# M32W_v1_0.net
KiCad netlist of a schematic drawn in EAGLE
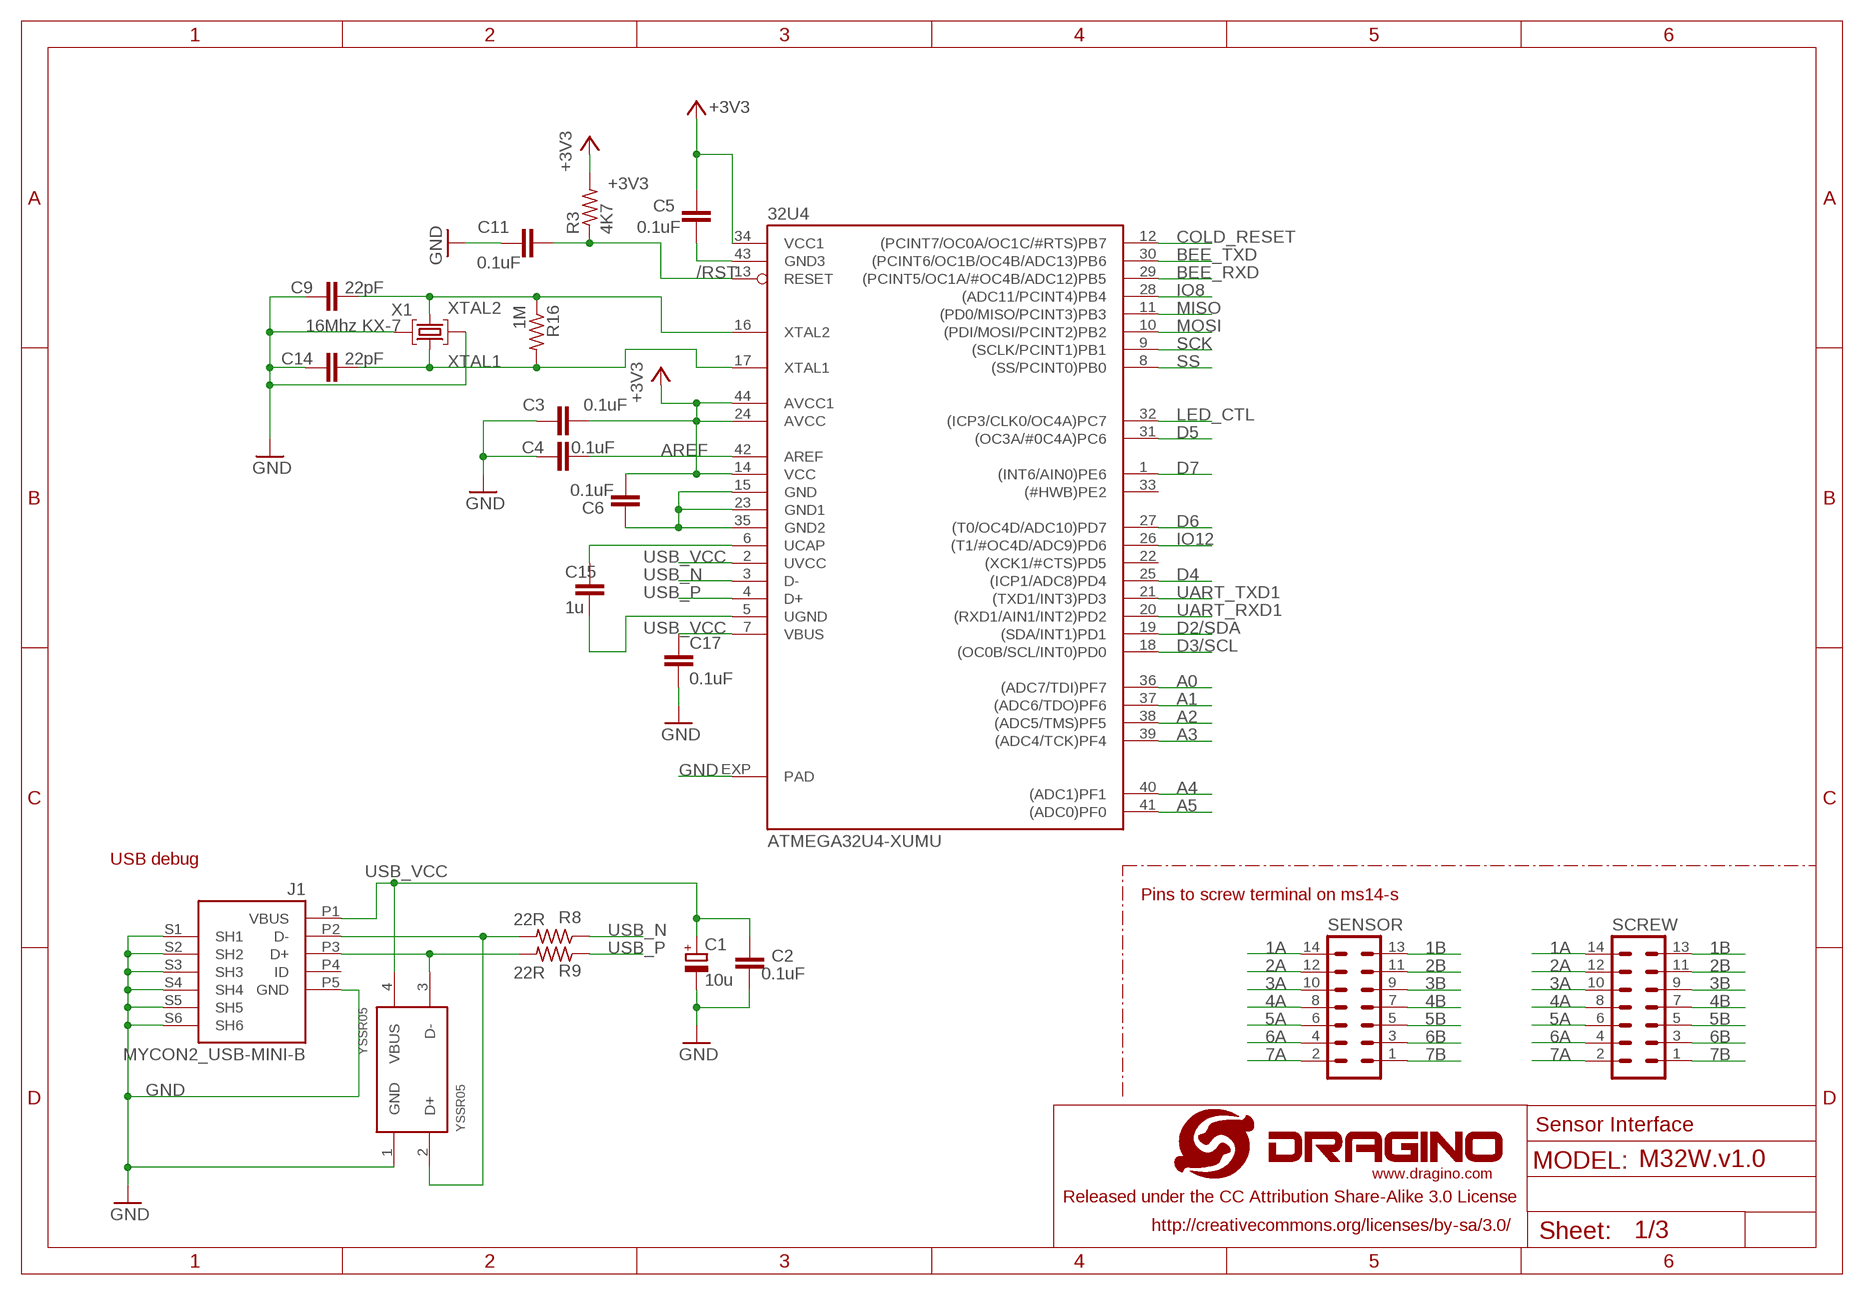
[diagram p0: schematic, sheet 1]
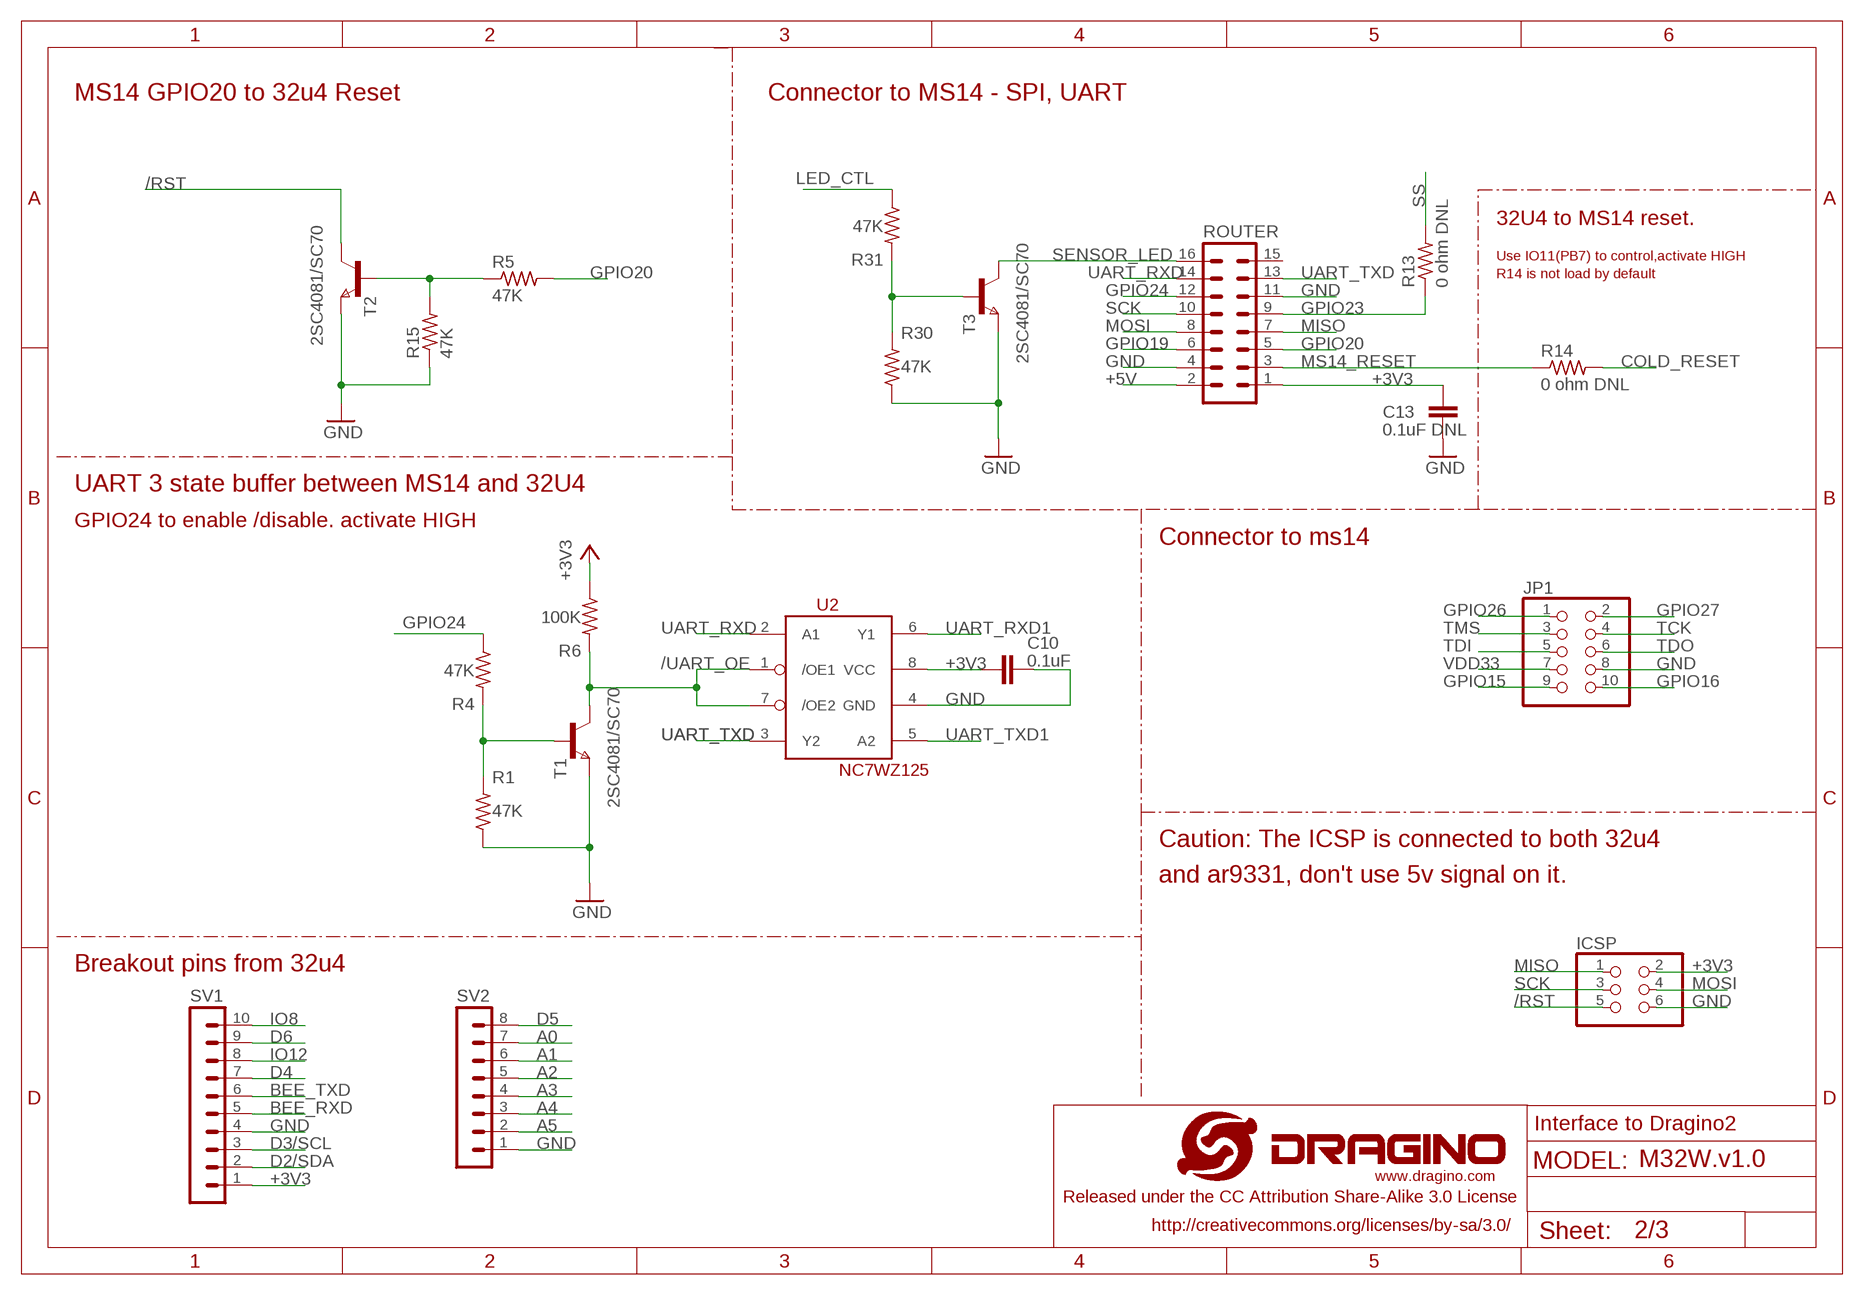
[diagram p1: schematic, sheet 2]
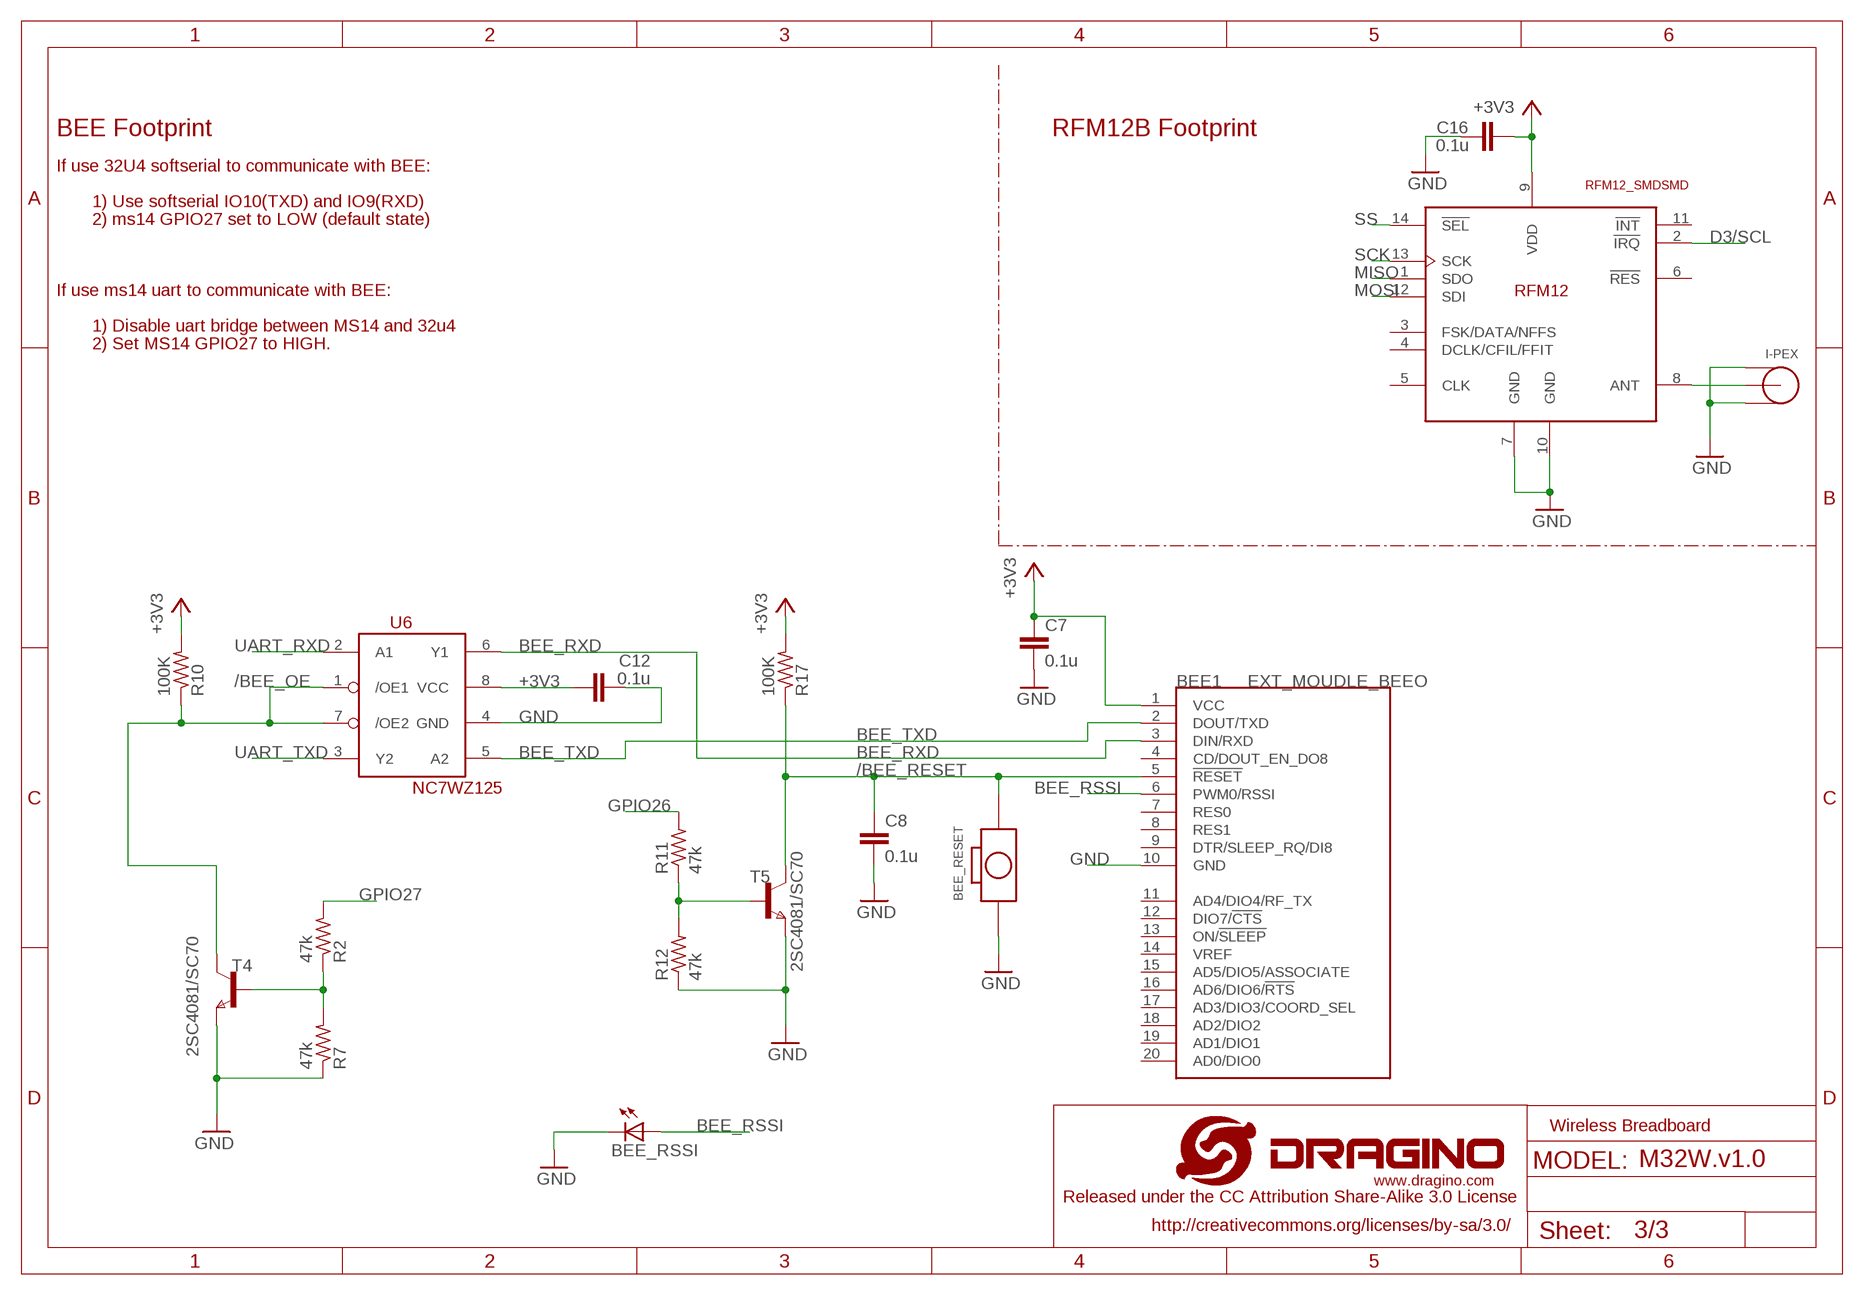
[diagram p2: schematic, sheet 3]

(export (version "E")
  (design (tool "Eeschema 10.0.6"))
  (components
    (comp (ref "32U4")
      (value "ATMEGA32U4-XUMU")
      (footprint "eagle-import:QFN44ML7X7")
      (libsource (lib "eagle-import") (part "ATMEGA32U4-XUMU"))
    )
    (comp (ref "C1")
      (value "10u")
      (footprint "eagle-import:SMC_B")
      (libsource (lib "eagle-import") (part "CPOL-EUSMCB"))
    )
    (comp (ref "C2")
      (value "0.1uF")
      (footprint "eagle-import:C0402")
      (libsource (lib "eagle-import") (part "C-EUC0402"))
    )
    (comp (ref "C3")
      (value "0.1uF")
      (footprint "eagle-import:C0402")
      (libsource (lib "eagle-import") (part "C-EUC0402"))
    )
    (comp (ref "C4")
      (value "0.1uF")
      (footprint "eagle-import:C0402")
      (libsource (lib "eagle-import") (part "C-EUC0402"))
    )
    (comp (ref "C5")
      (value "0.1uF")
      (footprint "eagle-import:C0402")
      (libsource (lib "eagle-import") (part "C-EUC0402"))
    )
    (comp (ref "C6")
      (value "0.1uF")
      (footprint "eagle-import:C0402")
      (libsource (lib "eagle-import") (part "C-EUC0402"))
    )
    (comp (ref "C9")
      (value "22pF")
      (footprint "eagle-import:C0402")
      (libsource (lib "eagle-import") (part "C-EUC0402"))
    )
    (comp (ref "C11")
      (value "0.1uF")
      (footprint "eagle-import:C0402")
      (libsource (lib "eagle-import") (part "C-EUC0402"))
    )
    (comp (ref "C14")
      (value "22pF")
      (footprint "eagle-import:C0402")
      (libsource (lib "eagle-import") (part "C-EUC0402"))
    )
    (comp (ref "C15")
      (value "1u")
      (footprint "eagle-import:C0402")
      (libsource (lib "eagle-import") (part "C-EUC0402"))
    )
    (comp (ref "C17")
      (value "0.1uF")
      (footprint "eagle-import:C0402")
      (libsource (lib "eagle-import") (part "C-EUC0402"))
    )
    (comp (ref "J1")
      (value "MYCON2_USB-MINI-B")
      (footprint "eagle-import:CON2_USB_MICRO_B_AT")
      (libsource (lib "eagle-import") (part "MYCON2_USB-MINI-B"))
    )
    (comp (ref "R3")
      (value "4K7")
      (footprint "eagle-import:R0402")
      (libsource (lib "eagle-import") (part "R-US_R0402"))
    )
    (comp (ref "R8")
      (value "22R")
      (footprint "eagle-import:R0402")
      (libsource (lib "eagle-import") (part "R-US_R0402"))
    )
    (comp (ref "R9")
      (value "22R")
      (footprint "eagle-import:R0402")
      (libsource (lib "eagle-import") (part "R-US_R0402"))
    )
    (comp (ref "R16")
      (value "1M")
      (footprint "eagle-import:R0402")
      (libsource (lib "eagle-import") (part "R-US_R0402"))
    )
    (comp (ref "SCREW")
      (value "MA07-2")
      (footprint "eagle-import:MA07-2")
      (fields (field (name "OC_FARNELL") "unknown") (field (name "OC_NEWARK") "unknown"))
      (libsource (lib "eagle-import") (part "MA07-2"))
    )
    (comp (ref "SENSOR")
      (value "MA07-2")
      (footprint "eagle-import:MA07-2")
      (libsource (lib "eagle-import") (part "MA07-2"))
    )
    (comp (ref "X1")
      (value "16Mhz KX-7")
      (footprint "eagle-import:CRYSTAL-3.2-2.5")
      (libsource (lib "eagle-import") (part "CRYSTAL-3.2-2.5"))
    )
    (comp (ref "YSSR05")
      (value "YSSR05")
      (footprint "eagle-import:SOT143")
      (libsource (lib "eagle-import") (part "YSSR05"))
    )
    (comp (ref "C10")
      (value "0.1uF")
      (footprint "eagle-import:C0402")
      (libsource (lib "eagle-import") (part "C-EUC0402"))
    )
    (comp (ref "C13")
      (value "0.1uF DNL")
      (footprint "eagle-import:C0402")
      (libsource (lib "eagle-import") (part "C-EUC0402"))
    )
    (comp (ref "ICSP")
      (value "PINHD-2X3")
      (footprint "eagle-import:2X03")
      (libsource (lib "eagle-import") (part "PINHD-2X3"))
    )
    (comp (ref "JP1")
      (value "PINHD-2X5_2.00")
      (footprint "eagle-import:2X05M")
      (libsource (lib "eagle-import") (part "PINHD-2X5_2.00"))
    )
    (comp (ref "R1")
      (value "47K")
      (footprint "eagle-import:R0402")
      (libsource (lib "eagle-import") (part "R-US_R0402"))
    )
    (comp (ref "R4")
      (value "47K")
      (footprint "eagle-import:R0402")
      (libsource (lib "eagle-import") (part "R-US_R0402"))
    )
    (comp (ref "R5")
      (value "47K")
      (footprint "eagle-import:R0402")
      (libsource (lib "eagle-import") (part "R-US_R0402"))
    )
    (comp (ref "R6")
      (value "100K")
      (footprint "eagle-import:R0402")
      (libsource (lib "eagle-import") (part "R-US_R0402"))
    )
    (comp (ref "R13")
      (value "0 ohm DNL")
      (footprint "eagle-import:R0402")
      (libsource (lib "eagle-import") (part "R-US_R0402"))
    )
    (comp (ref "R14")
      (value "0 ohm DNL")
      (footprint "eagle-import:R0402")
      (libsource (lib "eagle-import") (part "R-US_R0402"))
    )
    (comp (ref "R15")
      (value "47K")
      (footprint "eagle-import:R0402")
      (libsource (lib "eagle-import") (part "R-US_R0402"))
    )
    (comp (ref "R30")
      (value "47K")
      (footprint "eagle-import:R0402")
      (libsource (lib "eagle-import") (part "R-US_R0402"))
    )
    (comp (ref "R31")
      (value "47K")
      (footprint "eagle-import:R0402")
      (libsource (lib "eagle-import") (part "R-US_R0402"))
    )
    (comp (ref "ROUTER")
      (value "MA08-2")
      (footprint "eagle-import:MA08-2")
      (libsource (lib "eagle-import") (part "MA08-2"))
    )
    (comp (ref "SV1")
      (value "MA10-1")
      (footprint "eagle-import:MA10-1")
      (libsource (lib "eagle-import") (part "MA10-1"))
    )
    (comp (ref "SV2")
      (value "MA08-1")
      (footprint "eagle-import:MA08-1")
      (libsource (lib "eagle-import") (part "MA08-1"))
    )
    (comp (ref "T1")
      (value "2SC4081/SC70")
      (footprint "eagle-import:SOT323")
      (fields (field (name "MPN") "DSS4160U-7"))
      (libsource (lib "eagle-import") (part "NPNSOT323"))
    )
    (comp (ref "T2")
      (value "2SC4081/SC70")
      (footprint "eagle-import:SOT323")
      (fields
        (field (name "MPN") "DSS4160U-7")
        (field (name "MPN_1") "DSS4160U-7")
        (field (name "OC_FARNELL") "1710696")
        (field (name "OC_NEWARK") "25R4558")
      )
      (libsource (lib "eagle-import") (part "NPNSOT323"))
    )
    (comp (ref "T3")
      (value "2SC4081/SC70")
      (footprint "eagle-import:SOT323")
      (fields (field (name "MPN") "DSS4160U-7"))
      (libsource (lib "eagle-import") (part "NPNSOT323"))
    )
    (comp (ref "U$5")
      (value "LOGO-NEW")
      (footprint "eagle-import:LOGO-SILK-NEW")
      (libsource (lib "eagle-import") (part "LOGO-NEW"))
    )
    (comp (ref "U2")
      (value "NC7WZ125")
      (footprint "eagle-import:US8")
      (libsource (lib "eagle-import") (part "NC7WZ125"))
    )
    (comp (ref "BEE1")
      (value "EXT_MOUDLE_BEEO")
      (footprint "eagle-import:EXT_MOUDLE_BEE")
      (libsource (lib "eagle-import") (part "EXT_MOUDLE_BEEO"))
    )
    (comp (ref "BEE_RESET")
      (value "CPT_SMD_BOTTON_1_SMD")
      (footprint "eagle-import:CPT_SMD_BOTTON_1")
      (libsource (lib "eagle-import") (part "CPT_SMD_BOTTON_1_SMD"))
    )
    (comp (ref "BEE_RSSI")
      (value "LEDCHIP-LED0805")
      (footprint "eagle-import:CHIP-LED0805")
      (libsource (lib "eagle-import") (part "LEDCHIP-LED0805"))
    )
    (comp (ref "C7")
      (value "0.1u")
      (footprint "eagle-import:C0402")
      (libsource (lib "eagle-import") (part "C-EUC0402"))
    )
    (comp (ref "C8")
      (value "0.1u")
      (footprint "eagle-import:C0402")
      (libsource (lib "eagle-import") (part "C-EUC0402"))
    )
    (comp (ref "C12")
      (value "0.1u")
      (footprint "eagle-import:C0402")
      (libsource (lib "eagle-import") (part "C-EUC0402"))
    )
    (comp (ref "C16")
      (value "0.1u")
      (footprint "eagle-import:C0402")
      (libsource (lib "eagle-import") (part "C-EUC0402"))
    )
    (comp (ref "I-PEX")
      (value "I-PEX")
      (footprint "eagle-import:I-PEX")
      (libsource (lib "eagle-import") (part "I-PEX"))
    )
    (comp (ref "R2")
      (value "47k")
      (footprint "eagle-import:R0402")
      (libsource (lib "eagle-import") (part "R-US_R0402"))
    )
    (comp (ref "R7")
      (value "47k")
      (footprint "eagle-import:R0402")
      (libsource (lib "eagle-import") (part "R-US_R0402"))
    )
    (comp (ref "R10")
      (value "100K")
      (footprint "eagle-import:R0402")
      (libsource (lib "eagle-import") (part "R-US_R0402"))
    )
    (comp (ref "R11")
      (value "47k")
      (footprint "eagle-import:R0402")
      (libsource (lib "eagle-import") (part "R-US_R0402"))
    )
    (comp (ref "R12")
      (value "47k")
      (footprint "eagle-import:R0402")
      (libsource (lib "eagle-import") (part "R-US_R0402"))
    )
    (comp (ref "R17")
      (value "100K")
      (footprint "eagle-import:R0402")
      (libsource (lib "eagle-import") (part "R-US_R0402"))
    )
    (comp (ref "T4")
      (value "2SC4081/SC70")
      (footprint "eagle-import:SOT323")
      (fields (field (name "MPN") "DSS4160U-7"))
      (libsource (lib "eagle-import") (part "NPNSOT323"))
    )
    (comp (ref "T5")
      (value "2SC4081/SC70")
      (footprint "eagle-import:SOT323")
      (fields (field (name "MPN") "DSS4160U-7"))
      (libsource (lib "eagle-import") (part "NPNSOT323"))
    )
    (comp (ref "U$3")
      (value "RFM12_SMDSMD")
      (footprint "eagle-import:RFM12")
      (libsource (lib "eagle-import") (part "RFM12_SMDSMD"))
    )
    (comp (ref "U6")
      (value "NC7WZ125")
      (footprint "eagle-import:US8")
      (libsource (lib "eagle-import") (part "NC7WZ125"))
    )
  )
  (nets
    (net (code "1") (name "+3V3") (class "Default")
      (node (ref "32U4") (pin "14") (pinfunction "VCC_14") (pintype "power_in"))
      (node (ref "32U4") (pin "24") (pinfunction "AVCC_24") (pintype "power_in"))
      (node (ref "32U4") (pin "34") (pinfunction "VCC1_34") (pintype "power_in"))
      (node (ref "32U4") (pin "44") (pinfunction "AVCC1_44") (pintype "power_in"))
      (node (ref "BEE1") (pin "1") (pinfunction "VCC_1") (pintype "bidirectional"))
      (node (ref "C10") (pin "2") (pinfunction "2_2") (pintype "passive"))
      (node (ref "C12") (pin "1") (pinfunction "1_1") (pintype "passive"))
      (node (ref "C13") (pin "1") (pinfunction "1_1") (pintype "passive"))
      (node (ref "C16") (pin "2") (pinfunction "2_2") (pintype "passive"))
      (node (ref "C3") (pin "2") (pinfunction "2_2") (pintype "passive"))
      (node (ref "C5") (pin "1") (pinfunction "1_1") (pintype "passive"))
      (node (ref "C6") (pin "2") (pinfunction "2_2") (pintype "passive"))
      (node (ref "C7") (pin "1") (pinfunction "1_1") (pintype "passive"))
      (node (ref "ICSP") (pin "2") (pinfunction "2_2") (pintype "passive"))
      (node (ref "R10") (pin "2") (pinfunction "2_2") (pintype "passive"))
      (node (ref "R17") (pin "2") (pinfunction "2_2") (pintype "passive"))
      (node (ref "R3") (pin "2") (pinfunction "2_2") (pintype "passive"))
      (node (ref "R6") (pin "1") (pinfunction "1_1") (pintype "passive"))
      (node (ref "ROUTER") (pin "1") (pinfunction "1_1") (pintype "passive"))
      (node (ref "SV1") (pin "1") (pinfunction "1_1") (pintype "passive"))
      (node (ref "U$3") (pin "9") (pinfunction "VDD_9") (pintype "power_in"))
      (node (ref "U2") (pin "8") (pinfunction "VCC_8") (pintype "power_in"))
      (node (ref "U6") (pin "8") (pinfunction "VCC_8") (pintype "power_in"))
    )
    (net (code "2") (name "+5V") (class "Default")
      (node (ref "ROUTER") (pin "2") (pinfunction "2_2") (pintype "passive"))
    )
    (net (code "3") (name "1A") (class "Default")
      (node (ref "SCREW") (pin "14") (pinfunction "14_14") (pintype "passive"))
      (node (ref "SENSOR") (pin "14") (pinfunction "14_14") (pintype "passive"))
    )
    (net (code "4") (name "1B") (class "Default")
      (node (ref "SCREW") (pin "13") (pinfunction "13_13") (pintype "passive"))
      (node (ref "SENSOR") (pin "13") (pinfunction "13_13") (pintype "passive"))
    )
    (net (code "5") (name "2A") (class "Default")
      (node (ref "SCREW") (pin "12") (pinfunction "12_12") (pintype "passive"))
      (node (ref "SENSOR") (pin "12") (pinfunction "12_12") (pintype "passive"))
    )
    (net (code "6") (name "2B") (class "Default")
      (node (ref "SCREW") (pin "11") (pinfunction "11_11") (pintype "passive"))
      (node (ref "SENSOR") (pin "11") (pinfunction "11_11") (pintype "passive"))
    )
    (net (code "7") (name "3A") (class "Default")
      (node (ref "SCREW") (pin "10") (pinfunction "10_10") (pintype "passive"))
      (node (ref "SENSOR") (pin "10") (pinfunction "10_10") (pintype "passive"))
    )
    (net (code "8") (name "3B") (class "Default")
      (node (ref "SCREW") (pin "9") (pinfunction "9_9") (pintype "passive"))
      (node (ref "SENSOR") (pin "9") (pinfunction "9_9") (pintype "passive"))
    )
    (net (code "9") (name "4A") (class "Default")
      (node (ref "SCREW") (pin "8") (pinfunction "8_8") (pintype "passive"))
      (node (ref "SENSOR") (pin "8") (pinfunction "8_8") (pintype "passive"))
    )
    (net (code "10") (name "4B") (class "Default")
      (node (ref "SCREW") (pin "7") (pinfunction "7_7") (pintype "passive"))
      (node (ref "SENSOR") (pin "7") (pinfunction "7_7") (pintype "passive"))
    )
    (net (code "11") (name "5A") (class "Default")
      (node (ref "SCREW") (pin "6") (pinfunction "6_6") (pintype "passive"))
      (node (ref "SENSOR") (pin "6") (pinfunction "6_6") (pintype "passive"))
    )
    (net (code "12") (name "5B") (class "Default")
      (node (ref "SCREW") (pin "5") (pinfunction "5_5") (pintype "passive"))
      (node (ref "SENSOR") (pin "5") (pinfunction "5_5") (pintype "passive"))
    )
    (net (code "13") (name "6A") (class "Default")
      (node (ref "SCREW") (pin "4") (pinfunction "4_4") (pintype "passive"))
      (node (ref "SENSOR") (pin "4") (pinfunction "4_4") (pintype "passive"))
    )
    (net (code "14") (name "6B") (class "Default")
      (node (ref "SCREW") (pin "3") (pinfunction "3_3") (pintype "passive"))
      (node (ref "SENSOR") (pin "3") (pinfunction "3_3") (pintype "passive"))
    )
    (net (code "15") (name "7A") (class "Default")
      (node (ref "SCREW") (pin "2") (pinfunction "2_2") (pintype "passive"))
      (node (ref "SENSOR") (pin "2") (pinfunction "2_2") (pintype "passive"))
    )
    (net (code "16") (name "7B") (class "Default")
      (node (ref "SCREW") (pin "1") (pinfunction "1_1") (pintype "passive"))
      (node (ref "SENSOR") (pin "1") (pinfunction "1_1") (pintype "passive"))
    )
    (net (code "17") (name "A0") (class "Default")
      (node (ref "32U4") (pin "36") (pinfunction "(ADC7/TDI)PF7_36") (pintype "bidirectional"))
      (node (ref "SV2") (pin "7") (pinfunction "7_7") (pintype "passive"))
    )
    (net (code "18") (name "A1") (class "Default")
      (node (ref "32U4") (pin "37") (pinfunction "(ADC6/TDO)PF6_37") (pintype "bidirectional"))
      (node (ref "SV2") (pin "6") (pinfunction "6_6") (pintype "passive"))
    )
    (net (code "19") (name "A2") (class "Default")
      (node (ref "32U4") (pin "38") (pinfunction "(ADC5/TMS)PF5_38") (pintype "bidirectional"))
      (node (ref "SV2") (pin "5") (pinfunction "5_5") (pintype "passive"))
    )
    (net (code "20") (name "A3") (class "Default")
      (node (ref "32U4") (pin "39") (pinfunction "(ADC4/TCK)PF4_39") (pintype "bidirectional"))
      (node (ref "SV2") (pin "4") (pinfunction "4_4") (pintype "passive"))
    )
    (net (code "21") (name "A4") (class "Default")
      (node (ref "32U4") (pin "40") (pinfunction "(ADC1)PF1_40") (pintype "bidirectional"))
      (node (ref "SV2") (pin "3") (pinfunction "3_3") (pintype "passive"))
    )
    (net (code "22") (name "A5") (class "Default")
      (node (ref "32U4") (pin "41") (pinfunction "(ADC0)PF0_41") (pintype "bidirectional"))
      (node (ref "SV2") (pin "2") (pinfunction "2_2") (pintype "passive"))
    )
    (net (code "23") (name "AREF") (class "Default")
      (node (ref "32U4") (pin "42") (pinfunction "AREF_42") (pintype "power_in"))
      (node (ref "C4") (pin "2") (pinfunction "2_2") (pintype "passive"))
    )
    (net (code "24") (name "BEE_RSSI") (class "Default")
      (node (ref "BEE1") (pin "6") (pinfunction "PWM0/RSSI_6") (pintype "bidirectional"))
      (node (ref "BEE_RSSI") (pin "A") (pinfunction "A_A") (pintype "passive"))
    )
    (net (code "25") (name "BEE_RXD") (class "Default")
      (node (ref "32U4") (pin "29") (pinfunction "(PCINT5/OC1A/#OC4B/ADC12)PB5_29") (pintype "bidirectional"))
      (node (ref "BEE1") (pin "3") (pinfunction "DIN/RXD_3") (pintype "bidirectional"))
      (node (ref "SV1") (pin "5") (pinfunction "5_5") (pintype "passive"))
      (node (ref "U6") (pin "6") (pinfunction "Y1_6") (pintype "output"))
    )
    (net (code "26") (name "BEE_TXD") (class "Default")
      (node (ref "32U4") (pin "30") (pinfunction "(PCINT6/OC1B/OC4B/ADC13)PB6_30") (pintype "bidirectional"))
      (node (ref "BEE1") (pin "2") (pinfunction "DOUT/TXD_2") (pintype "bidirectional"))
      (node (ref "SV1") (pin "6") (pinfunction "6_6") (pintype "passive"))
      (node (ref "U6") (pin "5") (pinfunction "A2_5") (pintype "input"))
    )
    (net (code "27") (name "COLD_RESET") (class "Default")
      (node (ref "32U4") (pin "12") (pinfunction "(PCINT7/OC0A/OC1C/#RTS)PB7_12") (pintype "bidirectional"))
      (node (ref "R14") (pin "2") (pinfunction "2_2") (pintype "passive"))
    )
    (net (code "28") (name "D2{slash}SDA") (class "Default")
      (node (ref "32U4") (pin "19") (pinfunction "(SDA/INT1)PD1_19") (pintype "bidirectional"))
      (node (ref "SV1") (pin "2") (pinfunction "2_2") (pintype "passive"))
    )
    (net (code "29") (name "D3{slash}SCL") (class "Default")
      (node (ref "32U4") (pin "18") (pinfunction "(OC0B/SCL/INT0)PD0_18") (pintype "bidirectional"))
      (node (ref "SV1") (pin "3") (pinfunction "3_3") (pintype "passive"))
      (node (ref "U$3") (pin "2") (pinfunction "~{IRQ}_2") (pintype "output"))
    )
    (net (code "30") (name "D4") (class "Default")
      (node (ref "32U4") (pin "25") (pinfunction "(ICP1/ADC8)PD4_25") (pintype "bidirectional"))
      (node (ref "SV1") (pin "7") (pinfunction "7_7") (pintype "passive"))
    )
    (net (code "31") (name "D5") (class "Default")
      (node (ref "32U4") (pin "31") (pinfunction "(OC3A/#0C4A)PC6_31") (pintype "bidirectional"))
      (node (ref "SV2") (pin "8") (pinfunction "8_8") (pintype "passive"))
    )
    (net (code "32") (name "D6") (class "Default")
      (node (ref "32U4") (pin "27") (pinfunction "(T0/OC4D/ADC10)PD7_27") (pintype "bidirectional"))
      (node (ref "SV1") (pin "9") (pinfunction "9_9") (pintype "passive"))
    )
    (net (code "33") (name "D7") (class "Default")
      (node (ref "32U4") (pin "1") (pinfunction "(INT6/AIN0)PE6_1") (pintype "bidirectional"))
    )
    (net (code "34") (name "GND") (class "Default")
      (node (ref "32U4") (pin "15") (pinfunction "GND_15") (pintype "power_in"))
      (node (ref "32U4") (pin "23") (pinfunction "GND1_23") (pintype "power_in"))
      (node (ref "32U4") (pin "35") (pinfunction "GND2_35") (pintype "power_in"))
      (node (ref "32U4") (pin "43") (pinfunction "GND3_43") (pintype "power_in"))
      (node (ref "32U4") (pin "5") (pinfunction "UGND_5") (pintype "power_in"))
      (node (ref "32U4") (pin "EXP") (pinfunction "PAD_EXP") (pintype "power_in"))
      (node (ref "BEE1") (pin "10") (pinfunction "GND_10") (pintype "bidirectional"))
      (node (ref "BEE_RESET") (pin "1") (pinfunction "1_1") (pintype "bidirectional"))
      (node (ref "BEE_RSSI") (pin "C") (pinfunction "C_C") (pintype "passive"))
      (node (ref "C1") (pin "-") (pinfunction "-_-") (pintype "passive"))
      (node (ref "C10") (pin "1") (pinfunction "1_1") (pintype "passive"))
      (node (ref "C11") (pin "2") (pinfunction "2_2") (pintype "passive"))
      (node (ref "C12") (pin "2") (pinfunction "2_2") (pintype "passive"))
      (node (ref "C13") (pin "2") (pinfunction "2_2") (pintype "passive"))
      (node (ref "C14") (pin "1") (pinfunction "1_1") (pintype "passive"))
      (node (ref "C15") (pin "1") (pinfunction "1_1") (pintype "passive"))
      (node (ref "C16") (pin "1") (pinfunction "1_1") (pintype "passive"))
      (node (ref "C17") (pin "1") (pinfunction "1_1") (pintype "passive"))
      (node (ref "C2") (pin "2") (pinfunction "2_2") (pintype "passive"))
      (node (ref "C3") (pin "1") (pinfunction "1_1") (pintype "passive"))
      (node (ref "C4") (pin "1") (pinfunction "1_1") (pintype "passive"))
      (node (ref "C5") (pin "2") (pinfunction "2_2") (pintype "passive"))
      (node (ref "C6") (pin "1") (pinfunction "1_1") (pintype "passive"))
      (node (ref "C7") (pin "2") (pinfunction "2_2") (pintype "passive"))
      (node (ref "C8") (pin "2") (pinfunction "2_2") (pintype "passive"))
      (node (ref "C9") (pin "1") (pinfunction "1_1") (pintype "passive"))
      (node (ref "I-PEX") (pin "GND") (pinfunction "GND_GND") (pintype "passive"))
      (node (ref "I-PEX") (pin "GND1") (pinfunction "GND1_GND1") (pintype "passive"))
      (node (ref "ICSP") (pin "6") (pinfunction "6_6") (pintype "passive"))
      (node (ref "J1") (pin "P5") (pinfunction "GND_P5") (pintype "passive"))
      (node (ref "J1") (pin "S1") (pinfunction "SH1_S1") (pintype "passive"))
      (node (ref "J1") (pin "S2") (pinfunction "SH2_S2") (pintype "passive"))
      (node (ref "J1") (pin "S3") (pinfunction "SH3_S3") (pintype "passive"))
      (node (ref "J1") (pin "S4") (pinfunction "SH4_S4") (pintype "passive"))
      (node (ref "J1") (pin "S5") (pinfunction "SH5_S5") (pintype "passive"))
      (node (ref "J1") (pin "S6") (pinfunction "SH6_S6") (pintype "passive"))
      (node (ref "JP1") (pin "8") (pinfunction "8_8") (pintype "passive"))
      (node (ref "R1") (pin "1") (pinfunction "1_1") (pintype "passive"))
      (node (ref "R12") (pin "1") (pinfunction "1_1") (pintype "passive"))
      (node (ref "R15") (pin "1") (pinfunction "1_1") (pintype "passive"))
      (node (ref "R30") (pin "1") (pinfunction "1_1") (pintype "passive"))
      (node (ref "R7") (pin "1") (pinfunction "1_1") (pintype "passive"))
      (node (ref "ROUTER") (pin "11") (pinfunction "11_11") (pintype "passive"))
      (node (ref "ROUTER") (pin "4") (pinfunction "4_4") (pintype "passive"))
      (node (ref "SV1") (pin "4") (pinfunction "4_4") (pintype "passive"))
      (node (ref "SV2") (pin "1") (pinfunction "1_1") (pintype "passive"))
      (node (ref "T1") (pin "3") (pinfunction "E_3") (pintype "passive"))
      (node (ref "T2") (pin "3") (pinfunction "E_3") (pintype "passive"))
      (node (ref "T3") (pin "3") (pinfunction "E_3") (pintype "passive"))
      (node (ref "T4") (pin "3") (pinfunction "E_3") (pintype "passive"))
      (node (ref "T5") (pin "3") (pinfunction "E_3") (pintype "passive"))
      (node (ref "U$3") (pin "10") (pinfunction "GND_10") (pintype "passive"))
      (node (ref "U$3") (pin "7") (pinfunction "GND_7") (pintype "passive"))
      (node (ref "U2") (pin "4") (pinfunction "GND_4") (pintype "power_in"))
      (node (ref "U6") (pin "4") (pinfunction "GND_4") (pintype "power_in"))
      (node (ref "X1") (pin "2") (pinfunction "GND_2") (pintype "passive"))
      (node (ref "X1") (pin "4") (pinfunction "GND_4") (pintype "passive"))
      (node (ref "YSSR05") (pin "1") (pinfunction "GND_1") (pintype "bidirectional"))
    )
    (net (code "35") (name "GPIO15") (class "Default")
      (node (ref "JP1") (pin "9") (pinfunction "9_9") (pintype "passive"))
    )
    (net (code "36") (name "GPIO16") (class "Default")
      (node (ref "JP1") (pin "10") (pinfunction "10_10") (pintype "passive"))
    )
    (net (code "37") (name "GPIO19") (class "Default")
      (node (ref "ROUTER") (pin "6") (pinfunction "6_6") (pintype "passive"))
    )
    (net (code "38") (name "GPIO20") (class "Default")
      (node (ref "R5") (pin "2") (pinfunction "2_2") (pintype "passive"))
      (node (ref "ROUTER") (pin "5") (pinfunction "5_5") (pintype "passive"))
    )
    (net (code "39") (name "GPIO23") (class "Default")
      (node (ref "R13") (pin "1") (pinfunction "1_1") (pintype "passive"))
      (node (ref "ROUTER") (pin "9") (pinfunction "9_9") (pintype "passive"))
    )
    (net (code "40") (name "GPIO24") (class "Default")
      (node (ref "R4") (pin "1") (pinfunction "1_1") (pintype "passive"))
      (node (ref "ROUTER") (pin "12") (pinfunction "12_12") (pintype "passive"))
    )
    (net (code "41") (name "GPIO26") (class "Default")
      (node (ref "JP1") (pin "1") (pinfunction "1_1") (pintype "passive"))
      (node (ref "R11") (pin "2") (pinfunction "2_2") (pintype "passive"))
    )
    (net (code "42") (name "GPIO27") (class "Default")
      (node (ref "JP1") (pin "2") (pinfunction "2_2") (pintype "passive"))
      (node (ref "R2") (pin "2") (pinfunction "2_2") (pintype "passive"))
    )
    (net (code "43") (name "IO8") (class "Default")
      (node (ref "32U4") (pin "28") (pinfunction "(ADC11/PCINT4)PB4_28") (pintype "bidirectional"))
      (node (ref "SV1") (pin "10") (pinfunction "10_10") (pintype "passive"))
    )
    (net (code "44") (name "IO12") (class "Default")
      (node (ref "32U4") (pin "26") (pinfunction "(T1/#OC4D/ADC9)PD6_26") (pintype "bidirectional"))
      (node (ref "SV1") (pin "8") (pinfunction "8_8") (pintype "passive"))
    )
    (net (code "45") (name "LED_CTL") (class "Default")
      (node (ref "32U4") (pin "32") (pinfunction "(ICP3/CLK0/OC4A)PC7_32") (pintype "bidirectional"))
      (node (ref "R31") (pin "1") (pinfunction "1_1") (pintype "passive"))
    )
    (net (code "46") (name "MISO") (class "Default")
      (node (ref "32U4") (pin "11") (pinfunction "(PD0/MISO/PCINT3)PB3_11") (pintype "bidirectional"))
      (node (ref "ICSP") (pin "1") (pinfunction "1_1") (pintype "passive"))
      (node (ref "ROUTER") (pin "7") (pinfunction "7_7") (pintype "passive"))
      (node (ref "U$3") (pin "1") (pinfunction "SDO_1") (pintype "output"))
    )
    (net (code "47") (name "MOSI") (class "Default")
      (node (ref "32U4") (pin "10") (pinfunction "(PDI/MOSI/PCINT2)PB2_10") (pintype "bidirectional"))
      (node (ref "ICSP") (pin "4") (pinfunction "4_4") (pintype "passive"))
      (node (ref "ROUTER") (pin "8") (pinfunction "8_8") (pintype "passive"))
      (node (ref "U$3") (pin "12") (pinfunction "SDI_12") (pintype "input"))
    )
    (net (code "48") (name "MS14_RESET") (class "Default")
      (node (ref "R14") (pin "1") (pinfunction "1_1") (pintype "passive"))
      (node (ref "ROUTER") (pin "3") (pinfunction "3_3") (pintype "passive"))
    )
    (net (code "49") (name "Net-(32U4-UCAP)") (class "Default")
      (node (ref "32U4") (pin "6") (pinfunction "UCAP_6") (pintype "passive"))
      (node (ref "C15") (pin "2") (pinfunction "2_2") (pintype "passive"))
    )
    (net (code "50") (name "Net-(J1-D+)") (class "Default")
      (node (ref "J1") (pin "P3") (pinfunction "D+_P3") (pintype "bidirectional"))
      (node (ref "R9") (pin "2") (pinfunction "2_2") (pintype "passive"))
      (node (ref "YSSR05") (pin "3") (pinfunction "D-_3") (pintype "bidirectional"))
    )
    (net (code "51") (name "Net-(J1-D-)") (class "Default")
      (node (ref "J1") (pin "P2") (pinfunction "D-_P2") (pintype "bidirectional"))
      (node (ref "R8") (pin "2") (pinfunction "2_2") (pintype "passive"))
      (node (ref "YSSR05") (pin "2") (pinfunction "D+_2") (pintype "bidirectional"))
    )
    (net (code "52") (name "Net-(T1-B)") (class "Default")
      (node (ref "R1") (pin "2") (pinfunction "2_2") (pintype "passive"))
      (node (ref "R4") (pin "2") (pinfunction "2_2") (pintype "passive"))
      (node (ref "T1") (pin "2") (pinfunction "B_2") (pintype "passive"))
    )
    (net (code "53") (name "Net-(T2-B)") (class "Default")
      (node (ref "R15") (pin "2") (pinfunction "2_2") (pintype "passive"))
      (node (ref "R5") (pin "1") (pinfunction "1_1") (pintype "passive"))
      (node (ref "T2") (pin "2") (pinfunction "B_2") (pintype "passive"))
    )
    (net (code "54") (name "Net-(T3-B)") (class "Default")
      (node (ref "R30") (pin "2") (pinfunction "2_2") (pintype "passive"))
      (node (ref "R31") (pin "2") (pinfunction "2_2") (pintype "passive"))
      (node (ref "T3") (pin "2") (pinfunction "B_2") (pintype "passive"))
    )
    (net (code "55") (name "Net-(T4-B)") (class "Default")
      (node (ref "R2") (pin "1") (pinfunction "1_1") (pintype "passive"))
      (node (ref "R7") (pin "2") (pinfunction "2_2") (pintype "passive"))
      (node (ref "T4") (pin "2") (pinfunction "B_2") (pintype "passive"))
    )
    (net (code "56") (name "Net-(T5-B)") (class "Default")
      (node (ref "R11") (pin "1") (pinfunction "1_1") (pintype "passive"))
      (node (ref "R12") (pin "2") (pinfunction "2_2") (pintype "passive"))
      (node (ref "T5") (pin "2") (pinfunction "B_2") (pintype "passive"))
    )
    (net (code "57") (name "Net-(U$3-ANT)") (class "Default")
      (node (ref "I-PEX") (pin "SIG") (pinfunction "SIG_SIG") (pintype "passive"))
      (node (ref "U$3") (pin "8") (pinfunction "ANT_8") (pintype "bidirectional"))
    )
    (net (code "58") (name "SCK") (class "Default")
      (node (ref "32U4") (pin "9") (pinfunction "(SCLK/PCINT1)PB1_9") (pintype "bidirectional"))
      (node (ref "ICSP") (pin "3") (pinfunction "3_3") (pintype "passive"))
      (node (ref "ROUTER") (pin "10") (pinfunction "10_10") (pintype "passive"))
      (node (ref "U$3") (pin "13") (pinfunction "SCK_13") (pintype "input"))
    )
    (net (code "59") (name "SENSOR_LED") (class "Default")
      (node (ref "ROUTER") (pin "16") (pinfunction "16_16") (pintype "passive"))
      (node (ref "T3") (pin "1") (pinfunction "C_1") (pintype "passive"))
    )
    (net (code "60") (name "SS") (class "Default")
      (node (ref "32U4") (pin "8") (pinfunction "(SS/PCINT0)PB0_8") (pintype "bidirectional"))
      (node (ref "R13") (pin "2") (pinfunction "2_2") (pintype "passive"))
      (node (ref "U$3") (pin "14") (pinfunction "~{SEL}_14") (pintype "input"))
    )
    (net (code "61") (name "TCK") (class "Default")
      (node (ref "JP1") (pin "4") (pinfunction "4_4") (pintype "passive"))
    )
    (net (code "62") (name "TDI") (class "Default")
      (node (ref "JP1") (pin "5") (pinfunction "5_5") (pintype "passive"))
    )
    (net (code "63") (name "TDO") (class "Default")
      (node (ref "JP1") (pin "6") (pinfunction "6_6") (pintype "passive"))
    )
    (net (code "64") (name "TMS") (class "Default")
      (node (ref "JP1") (pin "3") (pinfunction "3_3") (pintype "passive"))
    )
    (net (code "65") (name "UART_RXD") (class "Default")
      (node (ref "ROUTER") (pin "14") (pinfunction "14_14") (pintype "passive"))
      (node (ref "U2") (pin "2") (pinfunction "A1_2") (pintype "input"))
      (node (ref "U6") (pin "2") (pinfunction "A1_2") (pintype "input"))
    )
    (net (code "66") (name "UART_RXD1") (class "Default")
      (node (ref "32U4") (pin "20") (pinfunction "(RXD1/AIN1/INT2)PD2_20") (pintype "bidirectional"))
      (node (ref "U2") (pin "6") (pinfunction "Y1_6") (pintype "output"))
    )
    (net (code "67") (name "UART_TXD") (class "Default")
      (node (ref "ROUTER") (pin "13") (pinfunction "13_13") (pintype "passive"))
      (node (ref "U2") (pin "3") (pinfunction "Y2_3") (pintype "output"))
      (node (ref "U6") (pin "3") (pinfunction "Y2_3") (pintype "output"))
    )
    (net (code "68") (name "UART_TXD1") (class "Default")
      (node (ref "32U4") (pin "21") (pinfunction "(TXD1/INT3)PD3_21") (pintype "bidirectional"))
      (node (ref "U2") (pin "5") (pinfunction "A2_5") (pintype "input"))
    )
    (net (code "69") (name "USB_N") (class "Default")
      (node (ref "32U4") (pin "3") (pinfunction "D-_3") (pintype "bidirectional"))
      (node (ref "R8") (pin "1") (pinfunction "1_1") (pintype "passive"))
    )
    (net (code "70") (name "USB_P") (class "Default")
      (node (ref "32U4") (pin "4") (pinfunction "D+_4") (pintype "bidirectional"))
      (node (ref "R9") (pin "1") (pinfunction "1_1") (pintype "passive"))
    )
    (net (code "71") (name "USB_VCC") (class "Default")
      (node (ref "32U4") (pin "2") (pinfunction "UVCC_2") (pintype "power_in"))
      (node (ref "32U4") (pin "7") (pinfunction "VBUS_7") (pintype "input"))
      (node (ref "C1") (pin "+") (pinfunction "+_+") (pintype "passive"))
      (node (ref "C17") (pin "2") (pinfunction "2_2") (pintype "passive"))
      (node (ref "C2") (pin "1") (pinfunction "1_1") (pintype "passive"))
      (node (ref "J1") (pin "P1") (pinfunction "VBUS_P1") (pintype "power_in"))
      (node (ref "YSSR05") (pin "4") (pinfunction "VBUS_4") (pintype "bidirectional"))
    )
    (net (code "72") (name "VDD33") (class "Default")
      (node (ref "JP1") (pin "7") (pinfunction "7_7") (pintype "passive"))
    )
    (net (code "73") (name "XTAL1") (class "Default")
      (node (ref "32U4") (pin "17") (pinfunction "XTAL1_17") (pintype "bidirectional"))
      (node (ref "C14") (pin "2") (pinfunction "2_2") (pintype "passive"))
      (node (ref "R16") (pin "2") (pinfunction "2_2") (pintype "passive"))
      (node (ref "X1") (pin "3") (pinfunction "C2_3") (pintype "passive"))
    )
    (net (code "74") (name "XTAL2") (class "Default")
      (node (ref "32U4") (pin "16") (pinfunction "XTAL2_16") (pintype "bidirectional"))
      (node (ref "C9") (pin "2") (pinfunction "2_2") (pintype "passive"))
      (node (ref "R16") (pin "1") (pinfunction "1_1") (pintype "passive"))
      (node (ref "X1") (pin "1") (pinfunction "C1_1") (pintype "passive"))
    )
    (net (code "75") (name "unconnected-(32U4-(#HWB)PE2-Pad33)") (class "Default")
      (node (ref "32U4") (pin "33") (pinfunction "(#HWB)PE2_33") (pintype "bidirectional"))
    )
    (net (code "76") (name "unconnected-(32U4-(XCK1{slash}#CTS)PD5-Pad22)") (class "Default")
      (node (ref "32U4") (pin "22") (pinfunction "(XCK1/#CTS)PD5_22") (pintype "bidirectional"))
    )
    (net (code "77") (name "unconnected-(BEE1-AD0{slash}DIO0-Pad20)") (class "Default")
      (node (ref "BEE1") (pin "20") (pinfunction "AD0/DIO0_20") (pintype "bidirectional"))
    )
    (net (code "78") (name "unconnected-(BEE1-AD1{slash}DIO1-Pad19)") (class "Default")
      (node (ref "BEE1") (pin "19") (pinfunction "AD1/DIO1_19") (pintype "bidirectional"))
    )
    (net (code "79") (name "unconnected-(BEE1-AD2{slash}DIO2-Pad18)") (class "Default")
      (node (ref "BEE1") (pin "18") (pinfunction "AD2/DIO2_18") (pintype "bidirectional"))
    )
    (net (code "80") (name "unconnected-(BEE1-AD3{slash}DIO3{slash}COORD_SEL-Pad17)") (class "Default")
      (node (ref "BEE1") (pin "17") (pinfunction "AD3/DIO3/COORD_SEL_17") (pintype "bidirectional"))
    )
    (net (code "81") (name "unconnected-(BEE1-AD4{slash}DIO4{slash}RF_TX-Pad11)") (class "Default")
      (node (ref "BEE1") (pin "11") (pinfunction "AD4/DIO4/RF_TX_11") (pintype "bidirectional"))
    )
    (net (code "82") (name "unconnected-(BEE1-AD5{slash}DIO5{slash}ASSOCIATE-Pad15)") (class "Default")
      (node (ref "BEE1") (pin "15") (pinfunction "AD5/DIO5/ASSOCIATE_15") (pintype "bidirectional"))
    )
    (net (code "83") (name "unconnected-(BEE1-AD6{slash}DIO6{slash}~{RTS}-Pad16)") (class "Default")
      (node (ref "BEE1") (pin "16") (pinfunction "AD6/DIO6/~{RTS}_16") (pintype "bidirectional"))
    )
    (net (code "84") (name "unconnected-(BEE1-CD{slash}DOUT_EN_DO8-Pad4)") (class "Default")
      (node (ref "BEE1") (pin "4") (pinfunction "CD/DOUT_EN_DO8_4") (pintype "bidirectional"))
    )
    (net (code "85") (name "unconnected-(BEE1-DIO7{slash}~{CTS}-Pad12)") (class "Default")
      (node (ref "BEE1") (pin "12") (pinfunction "DIO7/~{CTS}_12") (pintype "bidirectional"))
    )
    (net (code "86") (name "unconnected-(BEE1-DTR{slash}SLEEP_RQ{slash}DI8-Pad9)") (class "Default")
      (node (ref "BEE1") (pin "9") (pinfunction "DTR/SLEEP_RQ/DI8_9") (pintype "bidirectional"))
    )
    (net (code "87") (name "unconnected-(BEE1-ON{slash}~{SLEEP}-Pad13)") (class "Default")
      (node (ref "BEE1") (pin "13") (pinfunction "ON/~{SLEEP}_13") (pintype "bidirectional"))
    )
    (net (code "88") (name "unconnected-(BEE1-RES0-Pad7)") (class "Default")
      (node (ref "BEE1") (pin "7") (pinfunction "RES0_7") (pintype "bidirectional"))
    )
    (net (code "89") (name "unconnected-(BEE1-RES1-Pad8)") (class "Default")
      (node (ref "BEE1") (pin "8") (pinfunction "RES1_8") (pintype "bidirectional"))
    )
    (net (code "90") (name "unconnected-(BEE1-VREF-Pad14)") (class "Default")
      (node (ref "BEE1") (pin "14") (pinfunction "VREF_14") (pintype "bidirectional"))
    )
    (net (code "91") (name "unconnected-(J1-ID-PadP4)") (class "Default")
      (node (ref "J1") (pin "P4") (pinfunction "ID_P4") (pintype "bidirectional"))
    )
    (net (code "92") (name "unconnected-(ROUTER-Pad15)") (class "Default")
      (node (ref "ROUTER") (pin "15") (pinfunction "15_15") (pintype "passive"))
    )
    (net (code "93") (name "unconnected-(U$3-CLK-Pad5)") (class "Default")
      (node (ref "U$3") (pin "5") (pinfunction "CLK_5") (pintype "output"))
    )
    (net (code "94") (name "unconnected-(U$3-DCLK{slash}CFIL{slash}FFIT-Pad4)") (class "Default")
      (node (ref "U$3") (pin "4") (pinfunction "DCLK/CFIL/FFIT_4") (pintype "bidirectional"))
    )
    (net (code "95") (name "unconnected-(U$3-FSK{slash}DATA{slash}NFFS-Pad3)") (class "Default")
      (node (ref "U$3") (pin "3") (pinfunction "FSK/DATA/NFFS_3") (pintype "bidirectional"))
    )
    (net (code "96") (name "unconnected-(U$3-~{INT}-Pad11)") (class "Default")
      (node (ref "U$3") (pin "11") (pinfunction "~{INT}_11") (pintype "bidirectional"))
    )
    (net (code "97") (name "unconnected-(U$3-~{RES}-Pad6)") (class "Default")
      (node (ref "U$3") (pin "6") (pinfunction "~{RES}_6") (pintype "bidirectional"))
    )
    (net (code "98") (name "{slash}BEE_OE") (class "Default")
      (node (ref "R10") (pin "1") (pinfunction "1_1") (pintype "passive"))
      (node (ref "T4") (pin "1") (pinfunction "C_1") (pintype "passive"))
      (node (ref "U6") (pin "1") (pinfunction "/OE1_1") (pintype "input"))
      (node (ref "U6") (pin "7") (pinfunction "/OE2_7") (pintype "input"))
    )
    (net (code "99") (name "{slash}BEE_RESET") (class "Default")
      (node (ref "BEE1") (pin "5") (pinfunction "~{RESET}_5") (pintype "bidirectional"))
      (node (ref "BEE_RESET") (pin "P$2") (pinfunction "2_P$2") (pintype "bidirectional"))
      (node (ref "C8") (pin "1") (pinfunction "1_1") (pintype "passive"))
      (node (ref "R17") (pin "1") (pinfunction "1_1") (pintype "passive"))
      (node (ref "T5") (pin "1") (pinfunction "C_1") (pintype "passive"))
    )
    (net (code "100") (name "{slash}RST") (class "Default")
      (node (ref "32U4") (pin "13") (pinfunction "RESET_13") (pintype "input"))
      (node (ref "C11") (pin "1") (pinfunction "1_1") (pintype "passive"))
      (node (ref "ICSP") (pin "5") (pinfunction "5_5") (pintype "passive"))
      (node (ref "R3") (pin "1") (pinfunction "1_1") (pintype "passive"))
      (node (ref "T2") (pin "1") (pinfunction "C_1") (pintype "passive"))
    )
    (net (code "101") (name "{slash}UART_OE") (class "Default")
      (node (ref "R6") (pin "2") (pinfunction "2_2") (pintype "passive"))
      (node (ref "T1") (pin "1") (pinfunction "C_1") (pintype "passive"))
      (node (ref "U2") (pin "1") (pinfunction "/OE1_1") (pintype "input"))
      (node (ref "U2") (pin "7") (pinfunction "/OE2_7") (pintype "input"))
    )
  )
)
